# Sheet_AIO_Shield.net
KiCad netlist of a schematic drawn in Altium Designer
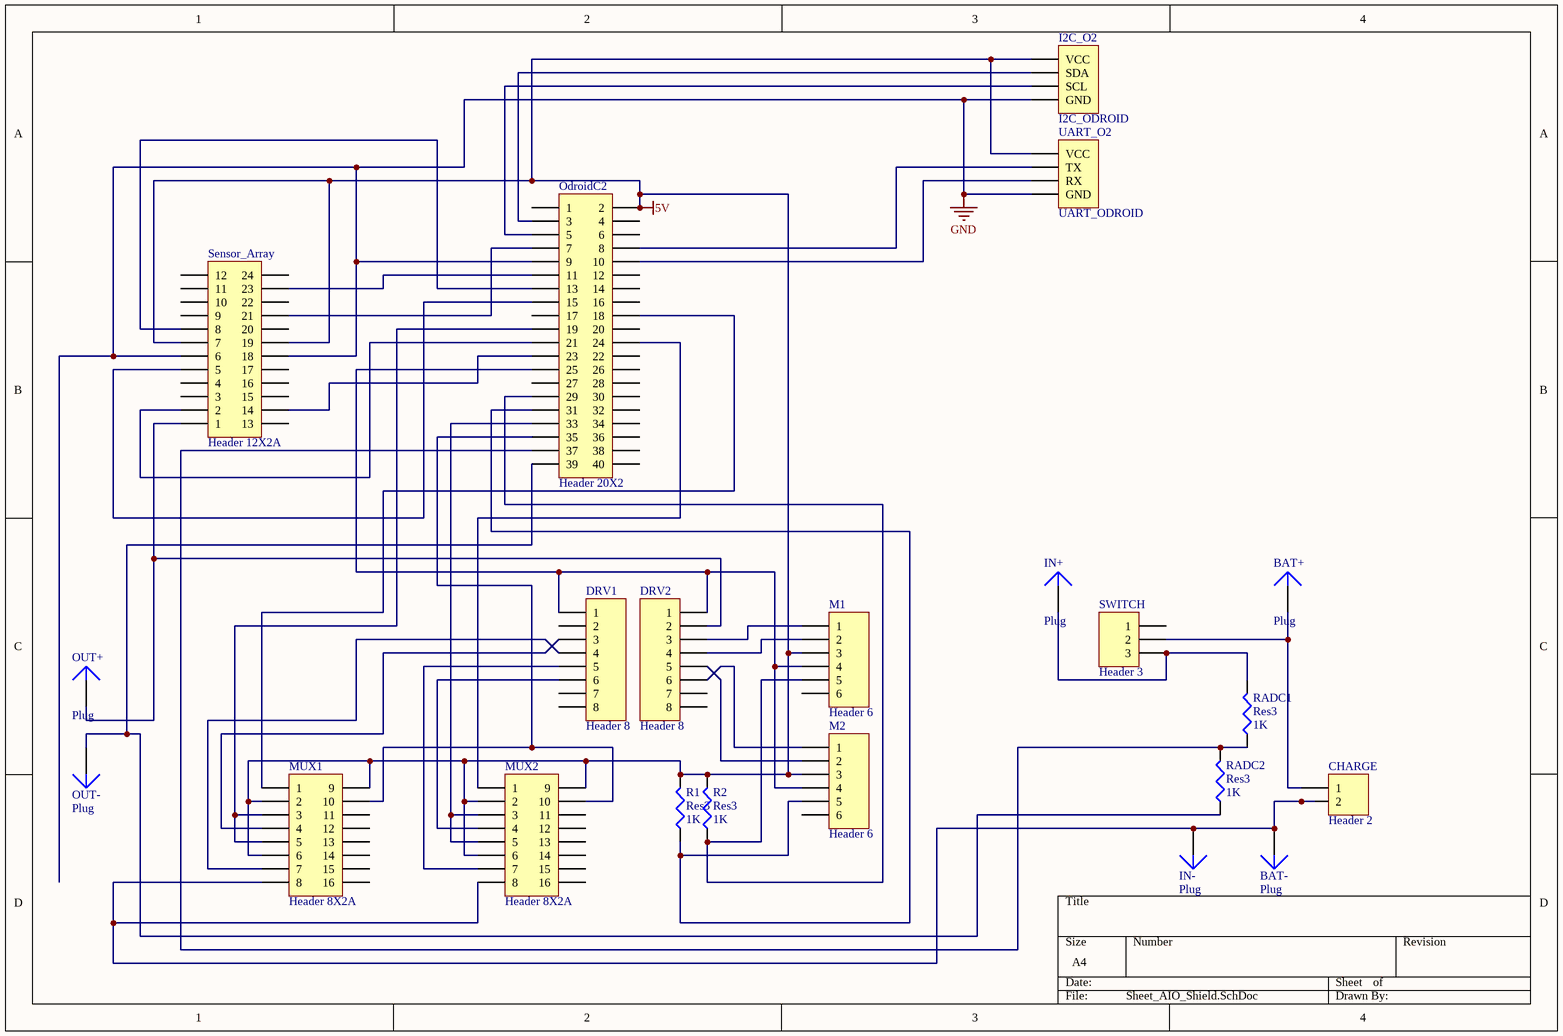
[diagram p0: Sheet_AIO_Shield.SchDoc]

(export (version "E")
  (design (tool "Eeschema 10.0.6"))
  (components
    (comp (ref "BAT+")
      (value "Plug")
      (footprint "PIN1")
      (fields (field (name "PUBLISHER") "Altium Limited"))
      (libsource (lib "Miscellaneous Connectors") (part "Plug"))
    )
    (comp (ref "BAT-")
      (value "Plug")
      (footprint "PIN1")
      (fields (field (name "PUBLISHER") "Altium Limited"))
      (libsource (lib "Miscellaneous Connectors") (part "Plug"))
    )
    (comp (ref "CHARGE")
      (value "Header 2")
      (footprint "HDR1X2")
      (description "Header, 2-Pin")
      (fields (field (name "PUBLISHER") "Altium Limited"))
      (libsource (lib "Miscellaneous Connectors") (part "Header 2"))
    )
    (comp (ref "DRV1")
      (value "Header 8")
      (footprint "HDR1X8")
      (description "Header, 8-Pin")
      (fields (field (name "PUBLISHER") "Altium Limited"))
      (libsource (lib "") (part "Header 8_1"))
    )
    (comp (ref "DRV2")
      (value "Header 8")
      (footprint "HDR1X8")
      (description "Header, 8-Pin")
      (fields (field (name "PUBLISHER") "Altium Limited"))
      (libsource (lib "Miscellaneous Connectors") (part "Header 8"))
    )
    (comp (ref "I2C_O2")
      (value "I2C_ODROID")
      (footprint "HDR1X4")
      (description "Header, 4-Pin")
      (fields (field (name "PUBLISHER") "Altium Limited"))
      (libsource (lib "Miscellaneous Connectors") (part "Header 4"))
    )
    (comp (ref "IN+")
      (value "Plug")
      (footprint "PIN1")
      (fields (field (name "PUBLISHER") "Altium Limited"))
      (libsource (lib "Miscellaneous Connectors") (part "Plug"))
    )
    (comp (ref "IN-")
      (value "Plug")
      (footprint "PIN1")
      (fields (field (name "PUBLISHER") "Altium Limited"))
      (libsource (lib "Miscellaneous Connectors") (part "Plug"))
    )
    (comp (ref "M1")
      (value "Header 6")
      (footprint "HDR1X6")
      (description "Header, 6-Pin")
      (fields (field (name "PUBLISHER") "Altium Limited"))
      (libsource (lib "Miscellaneous Connectors") (part "Header 6"))
    )
    (comp (ref "M2")
      (value "Header 6")
      (footprint "HDR1X6")
      (description "Header, 6-Pin")
      (fields (field (name "PUBLISHER") "Altium Limited"))
      (libsource (lib "Miscellaneous Connectors") (part "Header 6"))
    )
    (comp (ref "MUX1")
      (value "Header 8X2A")
      (footprint "N016")
      (description "Header, 8-Pin, Dual row")
      (fields (field (name "PUBLISHER") "Altium Limited"))
      (libsource (lib "Miscellaneous Connectors") (part "Header 8X2A"))
    )
    (comp (ref "MUX2")
      (value "Header 8X2A")
      (footprint "N016")
      (description "Header, 8-Pin, Dual row")
      (fields (field (name "PUBLISHER") "Altium Limited"))
      (libsource (lib "Miscellaneous Connectors") (part "Header 8X2A"))
    )
    (comp (ref "OdroidC2")
      (value "Header 20X2")
      (footprint "HDR2X20")
      (description "Header, 20-Pin, Dual row")
      (fields (field (name "PUBLISHER") "Altium Limited"))
      (libsource (lib "Miscellaneous Connectors") (part "Header 20X2"))
    )
    (comp (ref "OUT+")
      (value "Plug")
      (footprint "PIN1")
      (fields (field (name "PUBLISHER") "Altium Limited"))
      (libsource (lib "Miscellaneous Connectors") (part "Plug"))
    )
    (comp (ref "OUT-")
      (value "Plug")
      (footprint "PIN1")
      (fields (field (name "PUBLISHER") "Altium Limited"))
      (libsource (lib "Miscellaneous Connectors") (part "Plug"))
    )
    (comp (ref "R1")
      (value "Res3")
      (footprint "INDC3216")
      (description "Resistor")
      (fields (field (name "ALTIUM_VALUE") "1K") (field (name "PUBLISHER") "Altium Limited"))
      (libsource (lib "Miscellaneous Devices") (part "Res3"))
    )
    (comp (ref "R2")
      (value "Res3")
      (footprint "INDC3216")
      (description "Resistor")
      (fields (field (name "ALTIUM_VALUE") "1K") (field (name "PUBLISHER") "Altium Limited"))
      (libsource (lib "Miscellaneous Devices") (part "Res3"))
    )
    (comp (ref "RADC1")
      (value "Res3")
      (footprint "INDC3216")
      (description "Resistor")
      (fields (field (name "ALTIUM_VALUE") "1K") (field (name "PUBLISHER") "Altium Limited"))
      (libsource (lib "Miscellaneous Devices") (part "Res3"))
    )
    (comp (ref "RADC2")
      (value "Res3")
      (footprint "INDC3216")
      (description "Resistor")
      (fields (field (name "ALTIUM_VALUE") "1K") (field (name "PUBLISHER") "Altium Limited"))
      (libsource (lib "Miscellaneous Devices") (part "Res3"))
    )
    (comp (ref "Sensor_Array")
      (value "Header 12X2A")
      (footprint "HDR2X12_CEN")
      (description "Header, 12-Pin, Dual row")
      (fields (field (name "PUBLISHER") "Altium Limited"))
      (libsource (lib "Miscellaneous Connectors") (part "Header 12X2A"))
    )
    (comp (ref "SWITCH")
      (value "Header 3")
      (footprint "HDR1X3")
      (description "Header, 3-Pin")
      (fields (field (name "PUBLISHER") "Altium Limited"))
      (libsource (lib "Miscellaneous Connectors") (part "Header 3"))
    )
    (comp (ref "UART_O2")
      (value "UART_ODROID")
      (footprint "HDR1X4")
      (description "Header, 4-Pin")
      (fields (field (name "PUBLISHER") "Altium Limited"))
      (libsource (lib "") (part "Header 4_1"))
    )
  )
  (nets
    (net (code "1") (name "5V") (class "Default")
      (node (ref "I2C_O2") (pin "1") (pinfunction "VCC_1") (pintype "passive"))
      (node (ref "M1") (pin "3") (pinfunction "3_3") (pintype "passive"))
      (node (ref "M2") (pin "3") (pinfunction "3_3") (pintype "passive"))
      (node (ref "MUX1") (pin "16") (pinfunction "9_16") (pintype "passive"))
      (node (ref "MUX1") (pin "2") (pinfunction "2_2") (pintype "passive"))
      (node (ref "MUX1") (pin "6") (pinfunction "6_6") (pintype "passive"))
      (node (ref "MUX2") (pin "16") (pinfunction "9_16") (pintype "passive"))
      (node (ref "MUX2") (pin "2") (pinfunction "2_2") (pintype "passive"))
      (node (ref "MUX2") (pin "6") (pinfunction "6_6") (pintype "passive"))
      (node (ref "OdroidC2") (pin "2") (pinfunction "2_2") (pintype "passive"))
      (node (ref "R1") (pin "2") (pinfunction "2_2") (pintype "passive"))
      (node (ref "R2") (pin "2") (pinfunction "2_2") (pintype "passive"))
      (node (ref "Sensor_Array") (pin "19") (pinfunction "19_19") (pintype "passive"))
      (node (ref "Sensor_Array") (pin "7") (pinfunction "7_7") (pintype "passive"))
      (node (ref "UART_O2") (pin "1") (pinfunction "VCC_1") (pintype "passive"))
    )
    (net (code "2") (name "GND") (class "Default")
      (node (ref "I2C_O2") (pin "4") (pinfunction "GND_4") (pintype "passive"))
      (node (ref "OdroidC2") (pin "9") (pinfunction "9_9") (pintype "passive"))
      (node (ref "Sensor_Array") (pin "18") (pinfunction "18_18") (pintype "passive"))
      (node (ref "Sensor_Array") (pin "6") (pinfunction "6_6") (pintype "passive"))
      (node (ref "UART_O2") (pin "4") (pinfunction "GND_4") (pintype "passive"))
    )
    (net (code "3") (name "Net-(BAT+-Pad1)") (class "Default")
      (node (ref "BAT+") (pin "1") (pinfunction "1_1") (pintype "passive"))
      (node (ref "CHARGE") (pin "1") (pinfunction "1_1") (pintype "passive"))
      (node (ref "SWITCH") (pin "2") (pinfunction "2_2") (pintype "passive"))
    )
    (net (code "4") (name "Net-(BAT--Pad1)") (class "Default")
      (node (ref "BAT-") (pin "1") (pinfunction "1_1") (pintype "passive"))
      (node (ref "CHARGE") (pin "2") (pinfunction "2_2") (pintype "passive"))
      (node (ref "IN-") (pin "1") (pinfunction "1_1") (pintype "passive"))
      (node (ref "MUX1") (pin "8") (pinfunction "8_8") (pintype "passive"))
      (node (ref "MUX2") (pin "8") (pinfunction "8_8") (pintype "passive"))
    )
    (net (code "5") (name "Net-(DRV1-Pad1)") (class "Default")
      (node (ref "DRV1") (pin "1") (pinfunction "1_1") (pintype "passive"))
      (node (ref "DRV2") (pin "1") (pinfunction "1_1") (pintype "passive"))
      (node (ref "M1") (pin "4") (pinfunction "4_4") (pintype "passive"))
      (node (ref "M2") (pin "4") (pinfunction "4_4") (pintype "passive"))
      (node (ref "OdroidC2") (pin "25") (pinfunction "25_25") (pintype "passive"))
    )
    (net (code "6") (name "Net-(DRV1-Pad3)") (class "Default")
      (node (ref "DRV1") (pin "3") (pinfunction "3_3") (pintype "passive"))
      (node (ref "MUX1") (pin "4") (pinfunction "4_4") (pintype "passive"))
    )
    (net (code "7") (name "Net-(DRV1-Pad4)") (class "Default")
      (node (ref "DRV1") (pin "4") (pinfunction "4_4") (pintype "passive"))
      (node (ref "MUX1") (pin "7") (pinfunction "7_7") (pintype "passive"))
    )
    (net (code "8") (name "Net-(DRV1-Pad5)") (class "Default")
      (node (ref "DRV1") (pin "5") (pinfunction "5_5") (pintype "passive"))
      (node (ref "MUX2") (pin "7") (pinfunction "7_7") (pintype "passive"))
    )
    (net (code "9") (name "Net-(DRV1-Pad6)") (class "Default")
      (node (ref "DRV1") (pin "6") (pinfunction "6_6") (pintype "passive"))
      (node (ref "MUX2") (pin "4") (pinfunction "4_4") (pintype "passive"))
    )
    (net (code "10") (name "Net-(DRV2-Pad2)") (class "Default")
      (node (ref "DRV2") (pin "2") (pinfunction "2_2") (pintype "passive"))
      (node (ref "OUT+") (pin "1") (pinfunction "1_1") (pintype "passive"))
      (node (ref "Sensor_Array") (pin "1") (pinfunction "1_1") (pintype "passive"))
    )
    (net (code "11") (name "Net-(DRV2-Pad3)") (class "Default")
      (node (ref "DRV2") (pin "3") (pinfunction "3_3") (pintype "passive"))
      (node (ref "M1") (pin "1") (pinfunction "1_1") (pintype "passive"))
    )
    (net (code "12") (name "Net-(DRV2-Pad4)") (class "Default")
      (node (ref "DRV2") (pin "4") (pinfunction "4_4") (pintype "passive"))
      (node (ref "M1") (pin "2") (pinfunction "2_2") (pintype "passive"))
    )
    (net (code "13") (name "Net-(DRV2-Pad5)") (class "Default")
      (node (ref "DRV2") (pin "5") (pinfunction "5_5") (pintype "passive"))
      (node (ref "M2") (pin "2") (pinfunction "2_2") (pintype "passive"))
    )
    (net (code "14") (name "Net-(DRV2-Pad6)") (class "Default")
      (node (ref "DRV2") (pin "6") (pinfunction "6_6") (pintype "passive"))
      (node (ref "M2") (pin "1") (pinfunction "1_1") (pintype "passive"))
    )
    (net (code "15") (name "Net-(I2C_O2-SCL)") (class "Default")
      (node (ref "I2C_O2") (pin "3") (pinfunction "SCL_3") (pintype "passive"))
      (node (ref "OdroidC2") (pin "5") (pinfunction "5_5") (pintype "passive"))
    )
    (net (code "16") (name "Net-(I2C_O2-SDA)") (class "Default")
      (node (ref "I2C_O2") (pin "2") (pinfunction "SDA_2") (pintype "passive"))
      (node (ref "OdroidC2") (pin "3") (pinfunction "3_3") (pintype "passive"))
    )
    (net (code "17") (name "Net-(IN+-Pad1)") (class "Default")
      (node (ref "IN+") (pin "1") (pinfunction "1_1") (pintype "passive"))
      (node (ref "RADC1") (pin "2") (pinfunction "2_2") (pintype "passive"))
      (node (ref "SWITCH") (pin "3") (pinfunction "3_3") (pintype "passive"))
    )
    (net (code "18") (name "Net-(M1-Pad5)") (class "Default")
      (node (ref "M1") (pin "5") (pinfunction "5_5") (pintype "passive"))
      (node (ref "OdroidC2") (pin "29") (pinfunction "29_29") (pintype "passive"))
      (node (ref "R2") (pin "1") (pinfunction "1_1") (pintype "passive"))
    )
    (net (code "19") (name "Net-(M2-Pad5)") (class "Default")
      (node (ref "M2") (pin "5") (pinfunction "5_5") (pintype "passive"))
      (node (ref "OdroidC2") (pin "31") (pinfunction "31_31") (pintype "passive"))
      (node (ref "R1") (pin "1") (pinfunction "1_1") (pintype "passive"))
    )
    (net (code "20") (name "Net-(MUX1-10)") (class "Default")
      (node (ref "MUX1") (pin "15") (pinfunction "10_15") (pintype "passive"))
      (node (ref "MUX2") (pin "15") (pinfunction "10_15") (pintype "passive"))
      (node (ref "OdroidC2") (pin "35") (pinfunction "35_35") (pintype "passive"))
    )
    (net (code "21") (name "Net-(MUX1-Pad1)") (class "Default")
      (node (ref "MUX1") (pin "1") (pinfunction "1_1") (pintype "passive"))
      (node (ref "OdroidC2") (pin "18") (pinfunction "18_18") (pintype "passive"))
    )
    (net (code "22") (name "Net-(MUX1-Pad3)") (class "Default")
      (node (ref "MUX1") (pin "3") (pinfunction "3_3") (pintype "passive"))
      (node (ref "MUX1") (pin "5") (pinfunction "5_5") (pintype "passive"))
      (node (ref "OdroidC2") (pin "19") (pinfunction "19_19") (pintype "passive"))
    )
    (net (code "23") (name "Net-(MUX2-Pad1)") (class "Default")
      (node (ref "MUX2") (pin "1") (pinfunction "1_1") (pintype "passive"))
      (node (ref "OdroidC2") (pin "24") (pinfunction "24_24") (pintype "passive"))
    )
    (net (code "24") (name "Net-(MUX2-Pad3)") (class "Default")
      (node (ref "MUX2") (pin "3") (pinfunction "3_3") (pintype "passive"))
      (node (ref "MUX2") (pin "5") (pinfunction "5_5") (pintype "passive"))
      (node (ref "OdroidC2") (pin "33") (pinfunction "33_33") (pintype "passive"))
    )
    (net (code "25") (name "Net-(OUT--Pad1)") (class "Default")
      (node (ref "OUT-") (pin "1") (pinfunction "1_1") (pintype "passive"))
      (node (ref "OdroidC2") (pin "39") (pinfunction "39_39") (pintype "passive"))
      (node (ref "RADC2") (pin "1") (pinfunction "1_1") (pintype "passive"))
    )
    (net (code "26") (name "Net-(OdroidC2-Pad7)") (class "Default")
      (node (ref "OdroidC2") (pin "7") (pinfunction "7_7") (pintype "passive"))
      (node (ref "Sensor_Array") (pin "21") (pinfunction "21_21") (pintype "passive"))
    )
    (net (code "27") (name "Net-(OdroidC2-Pad11)") (class "Default")
      (node (ref "OdroidC2") (pin "11") (pinfunction "11_11") (pintype "passive"))
      (node (ref "Sensor_Array") (pin "23") (pinfunction "23_23") (pintype "passive"))
    )
    (net (code "28") (name "Net-(OdroidC2-Pad13)") (class "Default")
      (node (ref "OdroidC2") (pin "13") (pinfunction "13_13") (pintype "passive"))
      (node (ref "Sensor_Array") (pin "8") (pinfunction "8_8") (pintype "passive"))
    )
    (net (code "29") (name "Net-(OdroidC2-Pad15)") (class "Default")
      (node (ref "OdroidC2") (pin "15") (pinfunction "15_15") (pintype "passive"))
      (node (ref "Sensor_Array") (pin "5") (pinfunction "5_5") (pintype "passive"))
    )
    (net (code "30") (name "Net-(OdroidC2-Pad21)") (class "Default")
      (node (ref "OdroidC2") (pin "21") (pinfunction "21_21") (pintype "passive"))
      (node (ref "Sensor_Array") (pin "2") (pinfunction "2_2") (pintype "passive"))
    )
    (net (code "31") (name "Net-(OdroidC2-Pad23)") (class "Default")
      (node (ref "OdroidC2") (pin "23") (pinfunction "23_23") (pintype "passive"))
      (node (ref "Sensor_Array") (pin "14") (pinfunction "14_14") (pintype "passive"))
    )
    (net (code "32") (name "Net-(OdroidC2-Pad37)") (class "Default")
      (node (ref "OdroidC2") (pin "37") (pinfunction "37_37") (pintype "passive"))
      (node (ref "RADC1") (pin "1") (pinfunction "1_1") (pintype "passive"))
      (node (ref "RADC2") (pin "2") (pinfunction "2_2") (pintype "passive"))
    )
    (net (code "33") (name "Net-(UART_O2-RX)") (class "Default")
      (node (ref "OdroidC2") (pin "10") (pinfunction "10_10") (pintype "passive"))
      (node (ref "UART_O2") (pin "2") (pinfunction "RX_2") (pintype "passive"))
    )
    (net (code "34") (name "Net-(UART_O2-TX)") (class "Default")
      (node (ref "OdroidC2") (pin "8") (pinfunction "8_8") (pintype "passive"))
      (node (ref "UART_O2") (pin "3") (pinfunction "TX_3") (pintype "passive"))
    )
    (net (code "35") (name "unconnected-(DRV1-Pad2)") (class "Default")
      (node (ref "DRV1") (pin "2") (pinfunction "2_2") (pintype "passive"))
    )
    (net (code "36") (name "unconnected-(DRV1-Pad7)") (class "Default")
      (node (ref "DRV1") (pin "7") (pinfunction "7_7") (pintype "passive"))
    )
    (net (code "37") (name "unconnected-(DRV1-Pad8)") (class "Default")
      (node (ref "DRV1") (pin "8") (pinfunction "8_8") (pintype "passive"))
    )
    (net (code "38") (name "unconnected-(DRV2-Pad7)") (class "Default")
      (node (ref "DRV2") (pin "7") (pinfunction "7_7") (pintype "passive"))
    )
    (net (code "39") (name "unconnected-(DRV2-Pad8)") (class "Default")
      (node (ref "DRV2") (pin "8") (pinfunction "8_8") (pintype "passive"))
    )
    (net (code "40") (name "unconnected-(M1-Pad6)") (class "Default")
      (node (ref "M1") (pin "6") (pinfunction "6_6") (pintype "passive"))
    )
    (net (code "41") (name "unconnected-(M2-Pad6)") (class "Default")
      (node (ref "M2") (pin "6") (pinfunction "6_6") (pintype "passive"))
    )
    (net (code "42") (name "unconnected-(MUX1-11-Pad14)") (class "Default")
      (node (ref "MUX1") (pin "14") (pinfunction "11_14") (pintype "passive"))
    )
    (net (code "43") (name "unconnected-(MUX1-12-Pad13)") (class "Default")
      (node (ref "MUX1") (pin "13") (pinfunction "12_13") (pintype "passive"))
    )
    (net (code "44") (name "unconnected-(MUX1-13-Pad12)") (class "Default")
      (node (ref "MUX1") (pin "12") (pinfunction "13_12") (pintype "passive"))
    )
    (net (code "45") (name "unconnected-(MUX1-14-Pad11)") (class "Default")
      (node (ref "MUX1") (pin "11") (pinfunction "14_11") (pintype "passive"))
    )
    (net (code "46") (name "unconnected-(MUX1-15-Pad10)") (class "Default")
      (node (ref "MUX1") (pin "10") (pinfunction "15_10") (pintype "passive"))
    )
    (net (code "47") (name "unconnected-(MUX1-16-Pad9)") (class "Default")
      (node (ref "MUX1") (pin "9") (pinfunction "16_9") (pintype "passive"))
    )
    (net (code "48") (name "unconnected-(MUX2-11-Pad14)") (class "Default")
      (node (ref "MUX2") (pin "14") (pinfunction "11_14") (pintype "passive"))
    )
    (net (code "49") (name "unconnected-(MUX2-12-Pad13)") (class "Default")
      (node (ref "MUX2") (pin "13") (pinfunction "12_13") (pintype "passive"))
    )
    (net (code "50") (name "unconnected-(MUX2-13-Pad12)") (class "Default")
      (node (ref "MUX2") (pin "12") (pinfunction "13_12") (pintype "passive"))
    )
    (net (code "51") (name "unconnected-(MUX2-14-Pad11)") (class "Default")
      (node (ref "MUX2") (pin "11") (pinfunction "14_11") (pintype "passive"))
    )
    (net (code "52") (name "unconnected-(MUX2-15-Pad10)") (class "Default")
      (node (ref "MUX2") (pin "10") (pinfunction "15_10") (pintype "passive"))
    )
    (net (code "53") (name "unconnected-(MUX2-16-Pad9)") (class "Default")
      (node (ref "MUX2") (pin "9") (pinfunction "16_9") (pintype "passive"))
    )
    (net (code "54") (name "unconnected-(OdroidC2-Pad1)") (class "Default")
      (node (ref "OdroidC2") (pin "1") (pinfunction "1_1") (pintype "passive"))
    )
    (net (code "55") (name "unconnected-(OdroidC2-Pad4)") (class "Default")
      (node (ref "OdroidC2") (pin "4") (pinfunction "4_4") (pintype "passive"))
    )
    (net (code "56") (name "unconnected-(OdroidC2-Pad6)") (class "Default")
      (node (ref "OdroidC2") (pin "6") (pinfunction "6_6") (pintype "passive"))
    )
    (net (code "57") (name "unconnected-(OdroidC2-Pad12)") (class "Default")
      (node (ref "OdroidC2") (pin "12") (pinfunction "12_12") (pintype "passive"))
    )
    (net (code "58") (name "unconnected-(OdroidC2-Pad14)") (class "Default")
      (node (ref "OdroidC2") (pin "14") (pinfunction "14_14") (pintype "passive"))
    )
    (net (code "59") (name "unconnected-(OdroidC2-Pad16)") (class "Default")
      (node (ref "OdroidC2") (pin "16") (pinfunction "16_16") (pintype "passive"))
    )
    (net (code "60") (name "unconnected-(OdroidC2-Pad17)") (class "Default")
      (node (ref "OdroidC2") (pin "17") (pinfunction "17_17") (pintype "passive"))
    )
    (net (code "61") (name "unconnected-(OdroidC2-Pad20)") (class "Default")
      (node (ref "OdroidC2") (pin "20") (pinfunction "20_20") (pintype "passive"))
    )
    (net (code "62") (name "unconnected-(OdroidC2-Pad22)") (class "Default")
      (node (ref "OdroidC2") (pin "22") (pinfunction "22_22") (pintype "passive"))
    )
    (net (code "63") (name "unconnected-(OdroidC2-Pad26)") (class "Default")
      (node (ref "OdroidC2") (pin "26") (pinfunction "26_26") (pintype "passive"))
    )
    (net (code "64") (name "unconnected-(OdroidC2-Pad27)") (class "Default")
      (node (ref "OdroidC2") (pin "27") (pinfunction "27_27") (pintype "passive"))
    )
    (net (code "65") (name "unconnected-(OdroidC2-Pad28)") (class "Default")
      (node (ref "OdroidC2") (pin "28") (pinfunction "28_28") (pintype "passive"))
    )
    (net (code "66") (name "unconnected-(OdroidC2-Pad30)") (class "Default")
      (node (ref "OdroidC2") (pin "30") (pinfunction "30_30") (pintype "passive"))
    )
    (net (code "67") (name "unconnected-(OdroidC2-Pad32)") (class "Default")
      (node (ref "OdroidC2") (pin "32") (pinfunction "32_32") (pintype "passive"))
    )
    (net (code "68") (name "unconnected-(OdroidC2-Pad34)") (class "Default")
      (node (ref "OdroidC2") (pin "34") (pinfunction "34_34") (pintype "passive"))
    )
    (net (code "69") (name "unconnected-(OdroidC2-Pad36)") (class "Default")
      (node (ref "OdroidC2") (pin "36") (pinfunction "36_36") (pintype "passive"))
    )
    (net (code "70") (name "unconnected-(OdroidC2-Pad38)") (class "Default")
      (node (ref "OdroidC2") (pin "38") (pinfunction "38_38") (pintype "passive"))
    )
    (net (code "71") (name "unconnected-(OdroidC2-Pad40)") (class "Default")
      (node (ref "OdroidC2") (pin "40") (pinfunction "40_40") (pintype "passive"))
    )
    (net (code "72") (name "unconnected-(SWITCH-Pad1)") (class "Default")
      (node (ref "SWITCH") (pin "1") (pinfunction "1_1") (pintype "passive"))
    )
    (net (code "73") (name "unconnected-(Sensor_Array-Pad3)") (class "Default")
      (node (ref "Sensor_Array") (pin "3") (pinfunction "3_3") (pintype "passive"))
    )
    (net (code "74") (name "unconnected-(Sensor_Array-Pad4)") (class "Default")
      (node (ref "Sensor_Array") (pin "4") (pinfunction "4_4") (pintype "passive"))
    )
    (net (code "75") (name "unconnected-(Sensor_Array-Pad9)") (class "Default")
      (node (ref "Sensor_Array") (pin "9") (pinfunction "9_9") (pintype "passive"))
    )
    (net (code "76") (name "unconnected-(Sensor_Array-Pad10)") (class "Default")
      (node (ref "Sensor_Array") (pin "10") (pinfunction "10_10") (pintype "passive"))
    )
    (net (code "77") (name "unconnected-(Sensor_Array-Pad11)") (class "Default")
      (node (ref "Sensor_Array") (pin "11") (pinfunction "11_11") (pintype "passive"))
    )
    (net (code "78") (name "unconnected-(Sensor_Array-Pad12)") (class "Default")
      (node (ref "Sensor_Array") (pin "12") (pinfunction "12_12") (pintype "passive"))
    )
    (net (code "79") (name "unconnected-(Sensor_Array-Pad13)") (class "Default")
      (node (ref "Sensor_Array") (pin "13") (pinfunction "13_13") (pintype "passive"))
    )
    (net (code "80") (name "unconnected-(Sensor_Array-Pad15)") (class "Default")
      (node (ref "Sensor_Array") (pin "15") (pinfunction "15_15") (pintype "passive"))
    )
    (net (code "81") (name "unconnected-(Sensor_Array-Pad16)") (class "Default")
      (node (ref "Sensor_Array") (pin "16") (pinfunction "16_16") (pintype "passive"))
    )
    (net (code "82") (name "unconnected-(Sensor_Array-Pad17)") (class "Default")
      (node (ref "Sensor_Array") (pin "17") (pinfunction "17_17") (pintype "passive"))
    )
    (net (code "83") (name "unconnected-(Sensor_Array-Pad20)") (class "Default")
      (node (ref "Sensor_Array") (pin "20") (pinfunction "20_20") (pintype "passive"))
    )
    (net (code "84") (name "unconnected-(Sensor_Array-Pad22)") (class "Default")
      (node (ref "Sensor_Array") (pin "22") (pinfunction "22_22") (pintype "passive"))
    )
    (net (code "85") (name "unconnected-(Sensor_Array-Pad24)") (class "Default")
      (node (ref "Sensor_Array") (pin "24") (pinfunction "24_24") (pintype "passive"))
    )
  )
)
